# TOUG.net
KiCad netlist of a schematic drawn in EasyEDA
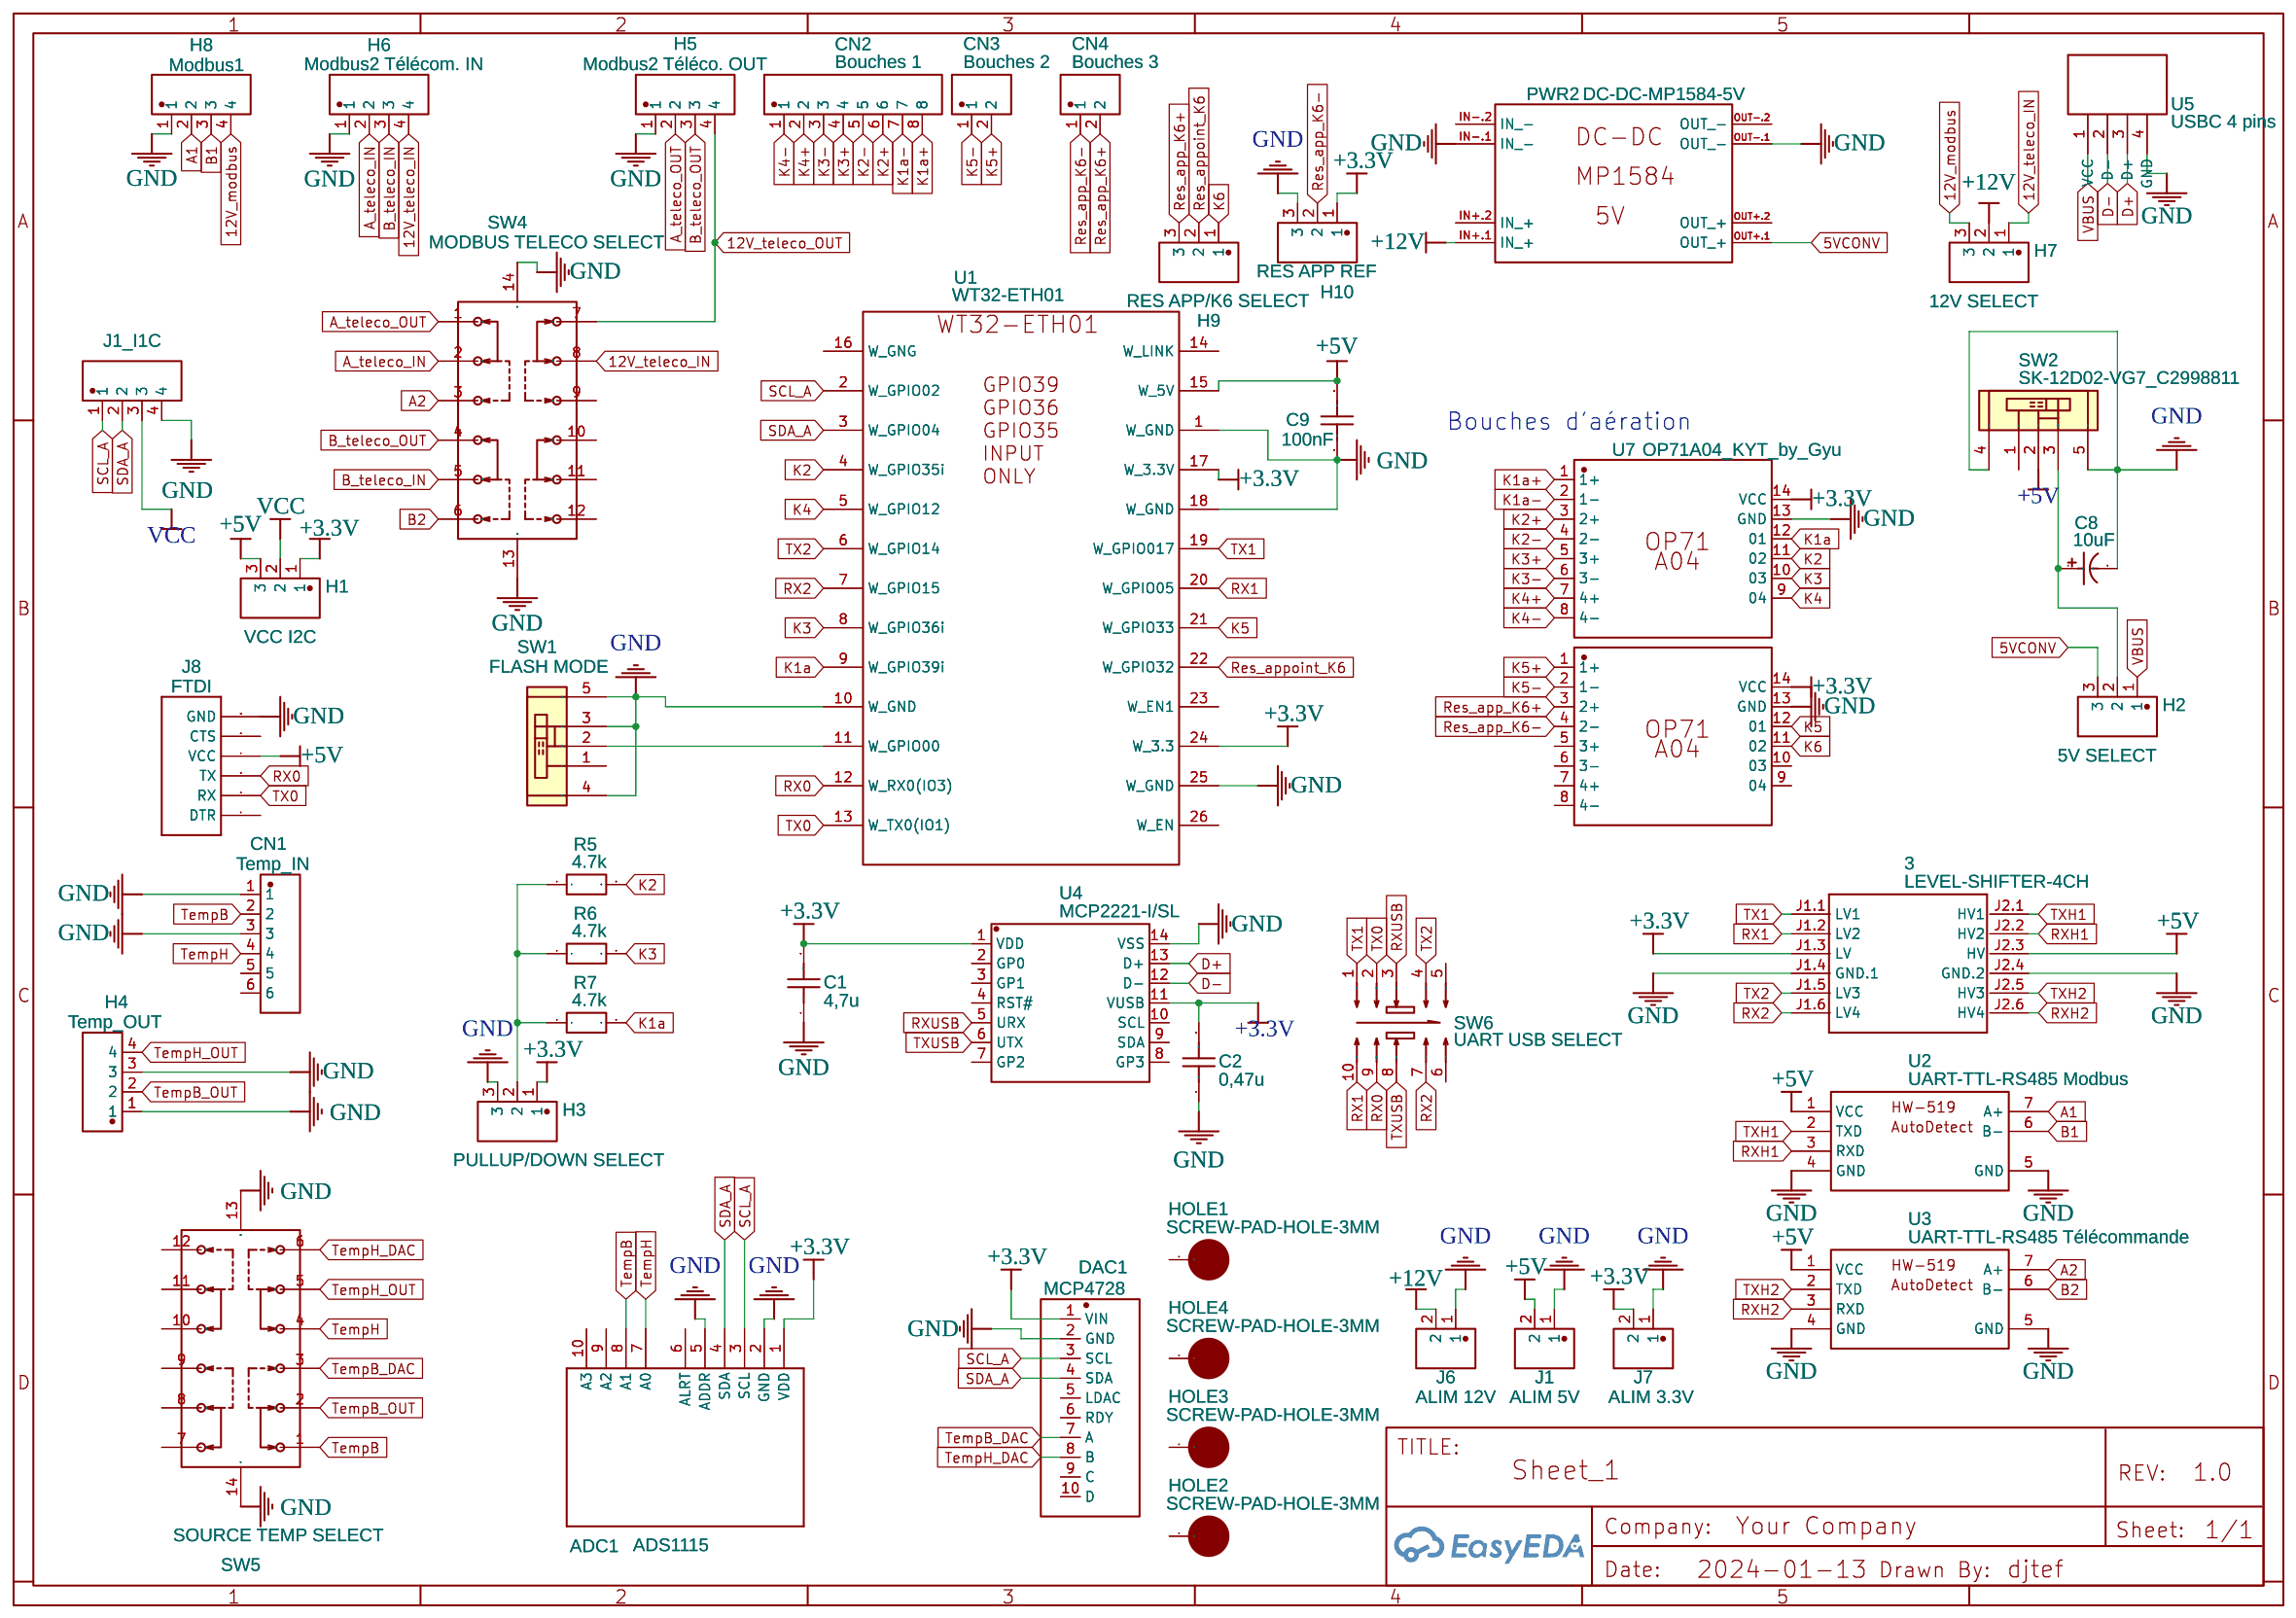
[diagram p0: schematic sheet]

(export (version "E")
  (design (tool "Eeschema 10.0.6"))
  (components
    (comp (ref "3") (value "LEVEL-SHIFTER-4CH") (libsource (lib "") (part "LEVEL-SHIFTER-4CH")))
    (comp (ref "ADC1") (value "ADS1115") (libsource (lib "") (part "ADC-4CH-ADS1115")))
    (comp (ref "C1") (value "4,7u") (libsource (lib "") (part "C_RAD-0.1_US")))
    (comp (ref "C2") (value "0,47u") (libsource (lib "") (part "C_RAD-0.1_US")))
    (comp (ref "C8")
      (value "10uF")
      (fields
        (field (name "Manufacturer Part") "GR106M050D11RR0VK2FP0")
        (field (name "Manufacturer") "CX(承兴)")
      )
      (libsource (lib "") (part "electrolytic capacitor 10UF 50V high frequency"))
    )
    (comp (ref "C9")
      (value "100nF")
      (fields (field (name "Manufacturer Part") "PE104J2A0501") (field (name "Manufacturer") "KYET(科雅)"))
      (libsource (lib "") (part "PE104J2A0501"))
    )
    (comp (ref "CN1")
      (value "Temp_IN")
      (fields (field (name "Manufacturer Part") "S06B-XASK-1(LF)(SN)") (field (name "Manufacturer") "JST"))
      (libsource (lib "") (part "S06B-XASK-1(LF)(SN)"))
    )
    (comp (ref "CN2")
      (value "Bouches 1")
      (fields (field (name "Manufacturer Part") "KF2EDGR-2.54-8P") (field (name "Manufacturer") "KEFA(科发)"))
      (libsource (lib "") (part "KF2EDGR-2.54-8P"))
    )
    (comp (ref "CN3")
      (value "Bouches 2")
      (fields (field (name "Manufacturer Part") "KF2EDGR-2.54-2P") (field (name "Manufacturer") "KEFA(科发)"))
      (libsource (lib "") (part "KF2EDGR-2.54-2P"))
    )
    (comp (ref "CN4")
      (value "Bouches 3")
      (fields (field (name "Manufacturer Part") "KF2EDGR-2.54-2P") (field (name "Manufacturer") "KEFA(科发)"))
      (libsource (lib "") (part "KF2EDGR-2.54-2P"))
    )
    (comp (ref "DAC1")
      (value "MCP4728")
      (fields (field (name "Manufacturer Part") "GY-MCP4728") (field (name "Manufacturer") "Aliexpress"))
      (libsource (lib "") (part "GY-MCP4728"))
    )
    (comp (ref "H1")
      (value "VCC I2C")
      (fields
        (field (name "Manufacturer Part") "DZ254R-11-03-63")
        (field (name "Manufacturer") "DEALON(德艺隆)")
      )
      (libsource (lib "") (part "DZ254R-11-03-63"))
    )
    (comp (ref "H2")
      (value "5V SELECT")
      (fields
        (field (name "Manufacturer Part") "DZ254R-11-03-63")
        (field (name "Manufacturer") "DEALON(德艺隆)")
      )
      (libsource (lib "") (part "DZ254R-11-03-63"))
    )
    (comp (ref "H3")
      (value "PULLUP/DOWN SELECT")
      (fields
        (field (name "Manufacturer Part") "DZ254R-11-03-63")
        (field (name "Manufacturer") "DEALON(德艺隆)")
      )
      (libsource (lib "") (part "DZ254R-11-03-63"))
    )
    (comp (ref "H4")
      (value "Temp_OUT")
      (fields (field (name "Manufacturer Part") "2.54-4P WZDK") (field (name "Manufacturer") "SHOU HAN(首韩)"))
      (libsource (lib "") (part "XH-2.54-4P_2"))
    )
    (comp (ref "H5")
      (value "Modbus2 Téléco. OUT")
      (fields (field (name "Manufacturer Part") "DL25018-4AWD-S") (field (name "Manufacturer") "DLL"))
      (libsource (lib "") (part "XH-2.54-4P"))
    )
    (comp (ref "H6")
      (value "Modbus2 Télécom. IN")
      (fields (field (name "Manufacturer Part") "2.54-4P WZDK") (field (name "Manufacturer") "SHOU HAN(首韩)"))
      (libsource (lib "") (part "XH-2.54-4P"))
    )
    (comp (ref "H7")
      (value "12V SELECT")
      (fields
        (field (name "Manufacturer Part") "DZ254R-11-03-63")
        (field (name "Manufacturer") "DEALON(德艺隆)")
      )
      (libsource (lib "") (part "DZ254R-11-03-63"))
    )
    (comp (ref "H8")
      (value "Modbus1")
      (fields (field (name "Manufacturer Part") "2.54-4P WZDK") (field (name "Manufacturer") "SHOU HAN(首韩)"))
      (libsource (lib "") (part "XH-2.54-4P"))
    )
    (comp (ref "H9")
      (value "RES APP/K6 SELECT")
      (fields
        (field (name "Manufacturer Part") "DZ254R-11-03-63")
        (field (name "Manufacturer") "DEALON(德艺隆)")
      )
      (libsource (lib "") (part "DZ254R-11-03-63"))
    )
    (comp (ref "H10")
      (value "RES APP REF")
      (fields
        (field (name "Manufacturer Part") "DZ254R-11-03-63")
        (field (name "Manufacturer") "DEALON(德艺隆)")
      )
      (libsource (lib "") (part "DZ254R-11-03-63"))
    )
    (comp (ref "HOLE1") (value "SCREW-PAD-HOLE-3MM") (libsource (lib "") (part "SCREW-PAD-HOLE-3MM")))
    (comp (ref "HOLE2") (value "SCREW-PAD-HOLE-3MM") (libsource (lib "") (part "SCREW-PAD-HOLE-3MM")))
    (comp (ref "HOLE3") (value "SCREW-PAD-HOLE-3MM") (libsource (lib "") (part "SCREW-PAD-HOLE-3MM")))
    (comp (ref "HOLE4") (value "SCREW-PAD-HOLE-3MM") (libsource (lib "") (part "SCREW-PAD-HOLE-3MM")))
    (comp (ref "J1")
      (value "ALIM 5V")
      (fields (field (name "Manufacturer Part") "KF2EDGR-5.08-2P") (field (name "Manufacturer") "KEFA(科发)"))
      (libsource (lib "") (part "KF2EDGR-5.08-2P"))
    )
    (comp (ref "J1_I1C")
      (value "I2C")
      (fields (field (name "Manufacturer Part") "2.54-4P WZDK") (field (name "Manufacturer") "SHOU HAN(首韩)"))
      (libsource (lib "") (part "XH-2.54-4P_1"))
    )
    (comp (ref "J6")
      (value "ALIM 12V")
      (fields (field (name "Manufacturer Part") "KF301-5.0-2P") (field (name "Manufacturer") "KEFA(科发)"))
      (libsource (lib "") (part "KF301-5.0-2P"))
    )
    (comp (ref "J7")
      (value "ALIM 3.3V")
      (fields (field (name "Manufacturer Part") "KF2EDGR-5.08-2P") (field (name "Manufacturer") "KEFA(科发)"))
      (libsource (lib "") (part "KF2EDGR-5.08-2P"))
    )
    (comp (ref "J8") (value "FTDI") (libsource (lib "") (part "FTDI HEADERX6")))
    (comp (ref "PWR2") (value "DC-DC-MP1584-5V") (libsource (lib "") (part "DC-DC-MP1584-5V")))
    (comp (ref "R5")
      (value "4.7k")
      (fields (field (name "Manufacturer Part") "CR1/4W-4K7±5%-ST52") (field (name "Manufacturer") "VO(翔胜)"))
      (libsource (lib "") (part "R_AXIAL-1.0_EU"))
    )
    (comp (ref "R6")
      (value "4.7k")
      (fields (field (name "Manufacturer Part") "CR1/4W-4K7±5%-ST52") (field (name "Manufacturer") "VO(翔胜)"))
      (libsource (lib "") (part "R_AXIAL-1.0_EU"))
    )
    (comp (ref "R7")
      (value "4.7k")
      (fields (field (name "Manufacturer Part") "CR1/4W-4K7±5%-ST52") (field (name "Manufacturer") "VO(翔胜)"))
      (libsource (lib "") (part "R_AXIAL-1.0_EU"))
    )
    (comp (ref "SW1")
      (value "FLASH MODE")
      (fields (field (name "Manufacturer Part") "SK-12D02-VG7") (field (name "Manufacturer") "DEALON(德艺隆)"))
      (libsource (lib "") (part "SK-12D02-VG7_C2998811"))
    )
    (comp (ref "SW2")
      (value "SK-12D02-VG7_C2998811")
      (fields (field (name "Manufacturer Part") "SK-12D02-VG7") (field (name "Manufacturer") "DEALON(德艺隆)"))
      (libsource (lib "") (part "SK-12D02-VG7_C2998811_1"))
    )
    (comp (ref "SW4")
      (value "MODBUS TELECO SELECT")
      (fields
        (field (name "Manufacturer Part") "KH-SS42D02-G3")
        (field (name "Manufacturer") "kinghelm(金航标)")
      )
      (libsource (lib "") (part "KH-SS42D02-G3"))
    )
    (comp (ref "SW5")
      (value "SOURCE TEMP SELECT")
      (fields
        (field (name "Manufacturer Part") "KH-SS42D02-G3")
        (field (name "Manufacturer") "kinghelm(金航标)")
      )
      (libsource (lib "") (part "KH-SS42D02-G3_1"))
    )
    (comp (ref "SW6")
      (value "UART USB SELECT")
      (fields (field (name "Manufacturer Part") "SS-24H03-G070") (field (name "Manufacturer") "G-Switch(品赞)"))
      (libsource (lib "") (part "SS-24H03-G070"))
    )
    (comp (ref "U1")
      (value "WT32-ETH01")
      (fields (field (name "Manufacturer") "Wireless-Tag"))
      (libsource (lib "") (part "WT32-ETH01"))
    )
    (comp (ref "U2") (value "UART-TTL-RS485 Modbus") (libsource (lib "") (part "UART-TTL-RS485_HW-519")))
    (comp (ref "U3")
      (value "UART-TTL-RS485 Télécommande")
      (libsource (lib "") (part "UART-TTL-RS485_HW-519"))
    )
    (comp (ref "U4")
      (value "MCP2221-I/SL")
      (fields (field (name "Manufacturer") "MICROCHIP(美国微芯)"))
      (libsource (lib "") (part "MCP2221-I/SL"))
    )
    (comp (ref "U5") (value "USBC 4 pins") (libsource (lib "") (part "USBC 4 pins")))
    (comp (ref "U7") (value "OP71A04_KYT_by_Gyu") (libsource (lib "") (part "OP71A04_KYT_by_Gyu")))
    (comp (ref "U14") (value "OP71A04_KYT_by_Gyu") (libsource (lib "") (part "OP71A04_KYT_by_Gyu")))
  )
  (nets
    (net (code "1") (name "+3.3V") (class "Default")
      (node (ref "3") (pin "J1.3") (pinfunction "LV_J1.3") (pintype "bidirectional"))
      (node (ref "ADC1") (pin "1") (pinfunction "VDD_1") (pintype "bidirectional"))
      (node (ref "C1") (pin "2") (pinfunction "2_2") (pintype "unspecified"))
      (node (ref "C2") (pin "2") (pinfunction "2_2") (pintype "unspecified"))
      (node (ref "DAC1") (pin "1") (pinfunction "VIN_1") (pintype "unspecified"))
      (node (ref "H1") (pin "1") (pinfunction "1_1") (pintype "unspecified"))
      (node (ref "H10") (pin "1") (pinfunction "1_1") (pintype "unspecified"))
      (node (ref "H3") (pin "1") (pinfunction "1_1") (pintype "unspecified"))
      (node (ref "J7") (pin "2") (pinfunction "2_2") (pintype "unspecified"))
      (node (ref "U1") (pin "17") (pinfunction "W_3.3V_17") (pintype "unspecified"))
      (node (ref "U1") (pin "24") (pinfunction "W_3.3_24") (pintype "unspecified"))
      (node (ref "U14") (pin "14") (pinfunction "VCC_14") (pintype "unspecified"))
      (node (ref "U4") (pin "1") (pinfunction "VDD_1") (pintype "unspecified"))
      (node (ref "U4") (pin "11") (pinfunction "VUSB_11") (pintype "unspecified"))
      (node (ref "U7") (pin "14") (pinfunction "VCC_14") (pintype "unspecified"))
    )
    (net (code "2") (name "+5V") (class "Default")
      (node (ref "3") (pin "J2.3") (pinfunction "HV_J2.3") (pintype "bidirectional"))
      (node (ref "C9") (pin "2") (pinfunction "2_2") (pintype "unspecified"))
      (node (ref "H1") (pin "3") (pinfunction "3_3") (pintype "unspecified"))
      (node (ref "J1") (pin "2") (pinfunction "2_2") (pintype "unspecified"))
      (node (ref "J8") (pin "4") (pinfunction "VCC_4") (pintype "unspecified"))
      (node (ref "SW2") (pin "2") (pinfunction "2_2") (pintype "input"))
      (node (ref "U1") (pin "15") (pinfunction "W_5V_15") (pintype "unspecified"))
      (node (ref "U2") (pin "1") (pinfunction "VCC_1") (pintype "unspecified"))
      (node (ref "U3") (pin "1") (pinfunction "VCC_1") (pintype "unspecified"))
    )
    (net (code "3") (name "+12V") (class "Default")
      (node (ref "H7") (pin "2") (pinfunction "2_2") (pintype "unspecified"))
      (node (ref "J6") (pin "2") (pinfunction "2_2") (pintype "unspecified"))
      (node (ref "PWR2") (pin "IN+.1") (pinfunction "IN_+_IN+.1") (pintype "unspecified"))
    )
    (net (code "4") (name "5VCONV") (class "Default")
      (node (ref "H2") (pin "3") (pinfunction "3_3") (pintype "unspecified"))
      (node (ref "PWR2") (pin "OUT+.1") (pinfunction "OUT_+_OUT+.1") (pintype "unspecified"))
    )
    (net (code "5") (name "12V_modbus") (class "Default")
      (node (ref "H7") (pin "3") (pinfunction "3_3") (pintype "unspecified"))
      (node (ref "H8") (pin "4") (pinfunction "4_4") (pintype "unspecified"))
    )
    (net (code "6") (name "12V_teleco_IN") (class "Default")
      (node (ref "H6") (pin "4") (pinfunction "4_4") (pintype "unspecified"))
      (node (ref "H7") (pin "1") (pinfunction "1_1") (pintype "unspecified"))
      (node (ref "SW4") (pin "8") (pinfunction "8_8") (pintype "unspecified"))
    )
    (net (code "7") (name "12V_teleco_OUT") (class "Default")
      (node (ref "H5") (pin "4") (pinfunction "4_4") (pintype "unspecified"))
      (node (ref "SW4") (pin "7") (pinfunction "7_7") (pintype "unspecified"))
    )
    (net (code "8") (name "A1") (class "Default")
      (node (ref "H8") (pin "2") (pinfunction "2_2") (pintype "unspecified"))
      (node (ref "U2") (pin "7") (pinfunction "A+_7") (pintype "unspecified"))
    )
    (net (code "9") (name "A2") (class "Default")
      (node (ref "SW4") (pin "3") (pinfunction "3_3") (pintype "unspecified"))
      (node (ref "U3") (pin "7") (pinfunction "A+_7") (pintype "unspecified"))
    )
    (net (code "10") (name "A_teleco_IN") (class "Default")
      (node (ref "H6") (pin "2") (pinfunction "2_2") (pintype "unspecified"))
      (node (ref "SW4") (pin "2") (pinfunction "2_2") (pintype "unspecified"))
    )
    (net (code "11") (name "A_teleco_OUT") (class "Default")
      (node (ref "H5") (pin "2") (pinfunction "2_2") (pintype "unspecified"))
      (node (ref "SW4") (pin "1") (pinfunction "1_1") (pintype "unspecified"))
    )
    (net (code "12") (name "B1") (class "Default")
      (node (ref "H8") (pin "3") (pinfunction "3_3") (pintype "unspecified"))
      (node (ref "U2") (pin "6") (pinfunction "B-_6") (pintype "unspecified"))
    )
    (net (code "13") (name "B2") (class "Default")
      (node (ref "SW4") (pin "6") (pinfunction "6_6") (pintype "unspecified"))
      (node (ref "U3") (pin "6") (pinfunction "B-_6") (pintype "unspecified"))
    )
    (net (code "14") (name "B_teleco_IN") (class "Default")
      (node (ref "H6") (pin "3") (pinfunction "3_3") (pintype "unspecified"))
      (node (ref "SW4") (pin "5") (pinfunction "5_5") (pintype "unspecified"))
    )
    (net (code "15") (name "B_teleco_OUT") (class "Default")
      (node (ref "H5") (pin "3") (pinfunction "3_3") (pintype "unspecified"))
      (node (ref "SW4") (pin "4") (pinfunction "4_4") (pintype "unspecified"))
    )
    (net (code "16") (name "D+") (class "Default")
      (node (ref "U4") (pin "13") (pinfunction "D+_13") (pintype "unspecified"))
      (node (ref "U5") (pin "3") (pinfunction "D+_3") (pintype "unspecified"))
    )
    (net (code "17") (name "D-") (class "Default")
      (node (ref "U4") (pin "12") (pinfunction "D-_12") (pintype "unspecified"))
      (node (ref "U5") (pin "2") (pinfunction "D-_2") (pintype "unspecified"))
    )
    (net (code "18") (name "GND") (class "Default")
      (node (ref "3") (pin "J1.4") (pinfunction "GND.1_J1.4") (pintype "bidirectional"))
      (node (ref "3") (pin "J2.4") (pinfunction "GND.2_J2.4") (pintype "bidirectional"))
      (node (ref "ADC1") (pin "2") (pinfunction "GND_2") (pintype "bidirectional"))
      (node (ref "ADC1") (pin "5") (pinfunction "ADDR_5") (pintype "bidirectional"))
      (node (ref "C1") (pin "1") (pinfunction "1_1") (pintype "unspecified"))
      (node (ref "C2") (pin "1") (pinfunction "1_1") (pintype "unspecified"))
      (node (ref "C8") (pin "2") (pinfunction "2_2") (pintype "input"))
      (node (ref "C9") (pin "1") (pinfunction "1_1") (pintype "unspecified"))
      (node (ref "CN1") (pin "1") (pinfunction "1_1") (pintype "unspecified"))
      (node (ref "CN1") (pin "3") (pinfunction "3_3") (pintype "unspecified"))
      (node (ref "DAC1") (pin "2") (pinfunction "GND_2") (pintype "unspecified"))
      (node (ref "H10") (pin "3") (pinfunction "3_3") (pintype "unspecified"))
      (node (ref "H3") (pin "3") (pinfunction "3_3") (pintype "unspecified"))
      (node (ref "H4") (pin "1") (pinfunction "1_1") (pintype "unspecified"))
      (node (ref "H4") (pin "3") (pinfunction "3_3") (pintype "unspecified"))
      (node (ref "H5") (pin "1") (pinfunction "1_1") (pintype "unspecified"))
      (node (ref "H6") (pin "1") (pinfunction "1_1") (pintype "unspecified"))
      (node (ref "H8") (pin "1") (pinfunction "1_1") (pintype "unspecified"))
      (node (ref "J1") (pin "1") (pinfunction "1_1") (pintype "unspecified"))
      (node (ref "J1_I1C") (pin "4") (pinfunction "4_4") (pintype "unspecified"))
      (node (ref "J6") (pin "1") (pinfunction "1_1") (pintype "unspecified"))
      (node (ref "J7") (pin "1") (pinfunction "1_1") (pintype "unspecified"))
      (node (ref "J8") (pin "6") (pinfunction "GND_6") (pintype "unspecified"))
      (node (ref "PWR2") (pin "IN-.1") (pinfunction "IN_-_IN-.1") (pintype "unspecified"))
      (node (ref "PWR2") (pin "OUT-.1") (pinfunction "OUT_-_OUT-.1") (pintype "unspecified"))
      (node (ref "SW1") (pin "3") (pinfunction "3_3") (pintype "input"))
      (node (ref "SW1") (pin "4") (pinfunction "4_4") (pintype "input"))
      (node (ref "SW1") (pin "5") (pinfunction "5_5") (pintype "input"))
      (node (ref "SW2") (pin "4") (pinfunction "4_4") (pintype "input"))
      (node (ref "SW2") (pin "5") (pinfunction "5_5") (pintype "input"))
      (node (ref "SW4") (pin "13") (pinfunction "13_13") (pintype "unspecified"))
      (node (ref "SW4") (pin "14") (pinfunction "14_14") (pintype "unspecified"))
      (node (ref "SW5") (pin "13") (pinfunction "13_13") (pintype "unspecified"))
      (node (ref "SW5") (pin "14") (pinfunction "14_14") (pintype "unspecified"))
      (node (ref "U1") (pin "1") (pinfunction "W_GND_1") (pintype "unspecified"))
      (node (ref "U1") (pin "10") (pinfunction "W_GND_10") (pintype "unspecified"))
      (node (ref "U1") (pin "18") (pinfunction "W_GND_18") (pintype "unspecified"))
      (node (ref "U1") (pin "25") (pinfunction "W_GND_25") (pintype "unspecified"))
      (node (ref "U14") (pin "13") (pinfunction "GND_13") (pintype "unspecified"))
      (node (ref "U2") (pin "4") (pinfunction "GND_4") (pintype "unspecified"))
      (node (ref "U2") (pin "5") (pinfunction "GND_5") (pintype "unspecified"))
      (node (ref "U3") (pin "4") (pinfunction "GND_4") (pintype "unspecified"))
      (node (ref "U3") (pin "5") (pinfunction "GND_5") (pintype "unspecified"))
      (node (ref "U4") (pin "14") (pinfunction "VSS_14") (pintype "unspecified"))
      (node (ref "U5") (pin "4") (pinfunction "GND_4") (pintype "unspecified"))
      (node (ref "U7") (pin "13") (pinfunction "GND_13") (pintype "unspecified"))
    )
    (net (code "19") (name "K1a") (class "Default")
      (node (ref "R7") (pin "2") (pinfunction "2_2") (pintype "unspecified"))
      (node (ref "U1") (pin "9") (pinfunction "W_GPIO39i_9") (pintype "unspecified"))
      (node (ref "U7") (pin "12") (pinfunction "01_12") (pintype "unspecified"))
    )
    (net (code "20") (name "K1a+") (class "Default")
      (node (ref "CN2") (pin "8") (pinfunction "8_8") (pintype "unspecified"))
      (node (ref "U7") (pin "1") (pinfunction "1+_1") (pintype "unspecified"))
    )
    (net (code "21") (name "K1a-") (class "Default")
      (node (ref "CN2") (pin "7") (pinfunction "7_7") (pintype "unspecified"))
      (node (ref "U7") (pin "2") (pinfunction "1-_2") (pintype "unspecified"))
    )
    (net (code "22") (name "K2") (class "Default")
      (node (ref "R5") (pin "2") (pinfunction "2_2") (pintype "unspecified"))
      (node (ref "U1") (pin "4") (pinfunction "W_GPIO35i_4") (pintype "unspecified"))
      (node (ref "U7") (pin "11") (pinfunction "02_11") (pintype "unspecified"))
    )
    (net (code "23") (name "K2+") (class "Default")
      (node (ref "CN2") (pin "6") (pinfunction "6_6") (pintype "unspecified"))
      (node (ref "U7") (pin "3") (pinfunction "2+_3") (pintype "unspecified"))
    )
    (net (code "24") (name "K2-") (class "Default")
      (node (ref "CN2") (pin "5") (pinfunction "5_5") (pintype "unspecified"))
      (node (ref "U7") (pin "4") (pinfunction "2-_4") (pintype "unspecified"))
    )
    (net (code "25") (name "K3") (class "Default")
      (node (ref "R6") (pin "2") (pinfunction "2_2") (pintype "unspecified"))
      (node (ref "U1") (pin "8") (pinfunction "W_GPIO36i_8") (pintype "unspecified"))
      (node (ref "U7") (pin "10") (pinfunction "03_10") (pintype "unspecified"))
    )
    (net (code "26") (name "K3+") (class "Default")
      (node (ref "CN2") (pin "4") (pinfunction "4_4") (pintype "unspecified"))
      (node (ref "U7") (pin "5") (pinfunction "3+_5") (pintype "unspecified"))
    )
    (net (code "27") (name "K3-") (class "Default")
      (node (ref "CN2") (pin "3") (pinfunction "3_3") (pintype "unspecified"))
      (node (ref "U7") (pin "6") (pinfunction "3-_6") (pintype "unspecified"))
    )
    (net (code "28") (name "K4") (class "Default")
      (node (ref "U1") (pin "5") (pinfunction "W_GPIO12_5") (pintype "unspecified"))
      (node (ref "U7") (pin "9") (pinfunction "04_9") (pintype "unspecified"))
    )
    (net (code "29") (name "K4+") (class "Default")
      (node (ref "CN2") (pin "2") (pinfunction "2_2") (pintype "unspecified"))
      (node (ref "U7") (pin "7") (pinfunction "4+_7") (pintype "unspecified"))
    )
    (net (code "30") (name "K4-") (class "Default")
      (node (ref "CN2") (pin "1") (pinfunction "1_1") (pintype "unspecified"))
      (node (ref "U7") (pin "8") (pinfunction "4-_8") (pintype "unspecified"))
    )
    (net (code "31") (name "K5") (class "Default")
      (node (ref "U1") (pin "21") (pinfunction "W_GPIO33_21") (pintype "unspecified"))
      (node (ref "U14") (pin "12") (pinfunction "01_12") (pintype "unspecified"))
    )
    (net (code "32") (name "K5+") (class "Default")
      (node (ref "CN3") (pin "2") (pinfunction "2_2") (pintype "unspecified"))
      (node (ref "U14") (pin "1") (pinfunction "1+_1") (pintype "unspecified"))
    )
    (net (code "33") (name "K5-") (class "Default")
      (node (ref "CN3") (pin "1") (pinfunction "1_1") (pintype "unspecified"))
      (node (ref "U14") (pin "2") (pinfunction "1-_2") (pintype "unspecified"))
    )
    (net (code "34") (name "K6") (class "Default")
      (node (ref "H9") (pin "1") (pinfunction "1_1") (pintype "unspecified"))
      (node (ref "U14") (pin "11") (pinfunction "02_11") (pintype "unspecified"))
    )
    (net (code "35") (name "Net-(C8-Pad1)") (class "Default")
      (node (ref "C8") (pin "1") (pinfunction "1_1") (pintype "input"))
      (node (ref "H2") (pin "2") (pinfunction "2_2") (pintype "unspecified"))
      (node (ref "SW2") (pin "3") (pinfunction "3_3") (pintype "input"))
    )
    (net (code "36") (name "Net-(H3-Pad2)") (class "Default")
      (node (ref "H3") (pin "2") (pinfunction "2_2") (pintype "unspecified"))
      (node (ref "R5") (pin "1") (pinfunction "1_1") (pintype "unspecified"))
      (node (ref "R6") (pin "1") (pinfunction "1_1") (pintype "unspecified"))
      (node (ref "R7") (pin "1") (pinfunction "1_1") (pintype "unspecified"))
    )
    (net (code "37") (name "Net-(U1-W_GPIO00)") (class "Default")
      (node (ref "SW1") (pin "2") (pinfunction "2_2") (pintype "input"))
      (node (ref "U1") (pin "11") (pinfunction "W_GPIO00_11") (pintype "unspecified"))
    )
    (net (code "38") (name "RX0") (class "Default")
      (node (ref "J8") (pin "3") (pinfunction "TX_3") (pintype "unspecified"))
      (node (ref "SW6") (pin "9") (pinfunction "9_9") (pintype "unspecified"))
      (node (ref "U1") (pin "12") (pinfunction "W_RX0(IO3)_12") (pintype "unspecified"))
    )
    (net (code "39") (name "RX1") (class "Default")
      (node (ref "3") (pin "J1.2") (pinfunction "LV2_J1.2") (pintype "bidirectional"))
      (node (ref "SW6") (pin "10") (pinfunction "10_10") (pintype "unspecified"))
      (node (ref "U1") (pin "20") (pinfunction "W_GPIO05_20") (pintype "unspecified"))
    )
    (net (code "40") (name "RX2") (class "Default")
      (node (ref "3") (pin "J1.6") (pinfunction "LV4_J1.6") (pintype "bidirectional"))
      (node (ref "SW6") (pin "7") (pinfunction "7_7") (pintype "unspecified"))
      (node (ref "U1") (pin "7") (pinfunction "W_GPIO15_7") (pintype "unspecified"))
    )
    (net (code "41") (name "RXH1") (class "Default")
      (node (ref "3") (pin "J2.2") (pinfunction "HV2_J2.2") (pintype "bidirectional"))
      (node (ref "U2") (pin "3") (pinfunction "RXD_3") (pintype "unspecified"))
    )
    (net (code "42") (name "RXH2") (class "Default")
      (node (ref "3") (pin "J2.6") (pinfunction "HV4_J2.6") (pintype "bidirectional"))
      (node (ref "U3") (pin "3") (pinfunction "RXD_3") (pintype "unspecified"))
    )
    (net (code "43") (name "RXUSB") (class "Default")
      (node (ref "SW6") (pin "3") (pinfunction "3_3") (pintype "unspecified"))
      (node (ref "U4") (pin "5") (pinfunction "URX_5") (pintype "unspecified"))
    )
    (net (code "44") (name "Res_app_K6+") (class "Default")
      (node (ref "CN4") (pin "2") (pinfunction "2_2") (pintype "unspecified"))
      (node (ref "H9") (pin "3") (pinfunction "3_3") (pintype "unspecified"))
      (node (ref "U14") (pin "3") (pinfunction "2+_3") (pintype "unspecified"))
    )
    (net (code "45") (name "Res_app_K6-") (class "Default")
      (node (ref "CN4") (pin "1") (pinfunction "1_1") (pintype "unspecified"))
      (node (ref "H10") (pin "2") (pinfunction "2_2") (pintype "unspecified"))
      (node (ref "U14") (pin "4") (pinfunction "2-_4") (pintype "unspecified"))
    )
    (net (code "46") (name "Res_appoint_K6") (class "Default")
      (node (ref "H9") (pin "2") (pinfunction "2_2") (pintype "unspecified"))
      (node (ref "U1") (pin "22") (pinfunction "W_GPIO32_22") (pintype "unspecified"))
    )
    (net (code "47") (name "SCL_A") (class "Default")
      (node (ref "ADC1") (pin "3") (pinfunction "SCL_3") (pintype "bidirectional"))
      (node (ref "DAC1") (pin "3") (pinfunction "SCL_3") (pintype "unspecified"))
      (node (ref "J1_I1C") (pin "1") (pinfunction "1_1") (pintype "unspecified"))
      (node (ref "U1") (pin "2") (pinfunction "W_GPIO02_2") (pintype "unspecified"))
    )
    (net (code "48") (name "SDA_A") (class "Default")
      (node (ref "ADC1") (pin "4") (pinfunction "SDA_4") (pintype "bidirectional"))
      (node (ref "DAC1") (pin "4") (pinfunction "SDA_4") (pintype "unspecified"))
      (node (ref "J1_I1C") (pin "2") (pinfunction "2_2") (pintype "unspecified"))
      (node (ref "U1") (pin "3") (pinfunction "W_GPIO04_3") (pintype "unspecified"))
    )
    (net (code "49") (name "TX0") (class "Default")
      (node (ref "J8") (pin "2") (pinfunction "RX_2") (pintype "unspecified"))
      (node (ref "SW6") (pin "2") (pinfunction "2_2") (pintype "unspecified"))
      (node (ref "U1") (pin "13") (pinfunction "W_TX0(IO1)_13") (pintype "unspecified"))
    )
    (net (code "50") (name "TX1") (class "Default")
      (node (ref "3") (pin "J1.1") (pinfunction "LV1_J1.1") (pintype "bidirectional"))
      (node (ref "SW6") (pin "1") (pinfunction "1_1") (pintype "unspecified"))
      (node (ref "U1") (pin "19") (pinfunction "W_GPIO017_19") (pintype "unspecified"))
    )
    (net (code "51") (name "TX2") (class "Default")
      (node (ref "3") (pin "J1.5") (pinfunction "LV3_J1.5") (pintype "bidirectional"))
      (node (ref "SW6") (pin "4") (pinfunction "4_4") (pintype "unspecified"))
      (node (ref "U1") (pin "6") (pinfunction "W_GPIO14_6") (pintype "unspecified"))
    )
    (net (code "52") (name "TXH1") (class "Default")
      (node (ref "3") (pin "J2.1") (pinfunction "HV1_J2.1") (pintype "bidirectional"))
      (node (ref "U2") (pin "2") (pinfunction "TXD_2") (pintype "unspecified"))
    )
    (net (code "53") (name "TXH2") (class "Default")
      (node (ref "3") (pin "J2.5") (pinfunction "HV3_J2.5") (pintype "bidirectional"))
      (node (ref "U3") (pin "2") (pinfunction "TXD_2") (pintype "unspecified"))
    )
    (net (code "54") (name "TXUSB") (class "Default")
      (node (ref "SW6") (pin "8") (pinfunction "8_8") (pintype "unspecified"))
      (node (ref "U4") (pin "6") (pinfunction "UTX_6") (pintype "unspecified"))
    )
    (net (code "55") (name "TempB") (class "Default")
      (node (ref "ADC1") (pin "8") (pinfunction "A1_8") (pintype "bidirectional"))
      (node (ref "CN1") (pin "2") (pinfunction "2_2") (pintype "unspecified"))
      (node (ref "SW5") (pin "1") (pinfunction "1_1") (pintype "unspecified"))
    )
    (net (code "56") (name "TempB_DAC") (class "Default")
      (node (ref "DAC1") (pin "7") (pinfunction "A_7") (pintype "unspecified"))
      (node (ref "SW5") (pin "3") (pinfunction "3_3") (pintype "unspecified"))
    )
    (net (code "57") (name "TempB_OUT") (class "Default")
      (node (ref "H4") (pin "2") (pinfunction "2_2") (pintype "unspecified"))
      (node (ref "SW5") (pin "2") (pinfunction "2_2") (pintype "unspecified"))
    )
    (net (code "58") (name "TempH") (class "Default")
      (node (ref "ADC1") (pin "7") (pinfunction "A0_7") (pintype "bidirectional"))
      (node (ref "CN1") (pin "4") (pinfunction "4_4") (pintype "unspecified"))
      (node (ref "SW5") (pin "4") (pinfunction "4_4") (pintype "unspecified"))
    )
    (net (code "59") (name "TempH_DAC") (class "Default")
      (node (ref "DAC1") (pin "8") (pinfunction "B_8") (pintype "unspecified"))
      (node (ref "SW5") (pin "6") (pinfunction "6_6") (pintype "unspecified"))
    )
    (net (code "60") (name "TempH_OUT") (class "Default")
      (node (ref "H4") (pin "4") (pinfunction "4_4") (pintype "unspecified"))
      (node (ref "SW5") (pin "5") (pinfunction "5_5") (pintype "unspecified"))
    )
    (net (code "61") (name "VBUS") (class "Default")
      (node (ref "H2") (pin "1") (pinfunction "1_1") (pintype "unspecified"))
      (node (ref "U5") (pin "1") (pinfunction "VCC_1") (pintype "unspecified"))
    )
    (net (code "62") (name "VCC") (class "Default")
      (node (ref "H1") (pin "2") (pinfunction "2_2") (pintype "unspecified"))
      (node (ref "J1_I1C") (pin "3") (pinfunction "3_3") (pintype "unspecified"))
    )
    (net (code "63") (name "unconnected-(ADC1-A2-Pad9)") (class "Default")
      (node (ref "ADC1") (pin "9") (pinfunction "A2_9") (pintype "bidirectional"))
    )
    (net (code "64") (name "unconnected-(ADC1-A3-Pad10)") (class "Default")
      (node (ref "ADC1") (pin "10") (pinfunction "A3_10") (pintype "bidirectional"))
    )
    (net (code "65") (name "unconnected-(ADC1-ALRT-Pad6)") (class "Default")
      (node (ref "ADC1") (pin "6") (pinfunction "ALRT_6") (pintype "bidirectional"))
    )
    (net (code "66") (name "unconnected-(CN1-Pad5)") (class "Default")
      (node (ref "CN1") (pin "5") (pinfunction "5_5") (pintype "unspecified"))
    )
    (net (code "67") (name "unconnected-(CN1-Pad6)") (class "Default")
      (node (ref "CN1") (pin "6") (pinfunction "6_6") (pintype "unspecified"))
    )
    (net (code "68") (name "unconnected-(DAC1-C-Pad9)") (class "Default")
      (node (ref "DAC1") (pin "9") (pinfunction "C_9") (pintype "unspecified"))
    )
    (net (code "69") (name "unconnected-(DAC1-D-Pad10)") (class "Default")
      (node (ref "DAC1") (pin "10") (pinfunction "D_10") (pintype "unspecified"))
    )
    (net (code "70") (name "unconnected-(DAC1-LDAC-Pad5)") (class "Default")
      (node (ref "DAC1") (pin "5") (pinfunction "LDAC_5") (pintype "unspecified"))
    )
    (net (code "71") (name "unconnected-(DAC1-RDY-Pad6)") (class "Default")
      (node (ref "DAC1") (pin "6") (pinfunction "RDY_6") (pintype "unspecified"))
    )
    (net (code "72") (name "unconnected-(HOLE1-Pad1)") (class "Default")
      (node (ref "HOLE1") (pin "1") (pinfunction "1_1") (pintype "unspecified"))
    )
    (net (code "73") (name "unconnected-(HOLE2-Pad1)") (class "Default")
      (node (ref "HOLE2") (pin "1") (pinfunction "1_1") (pintype "unspecified"))
    )
    (net (code "74") (name "unconnected-(HOLE3-Pad1)") (class "Default")
      (node (ref "HOLE3") (pin "1") (pinfunction "1_1") (pintype "unspecified"))
    )
    (net (code "75") (name "unconnected-(HOLE4-Pad1)") (class "Default")
      (node (ref "HOLE4") (pin "1") (pinfunction "1_1") (pintype "unspecified"))
    )
    (net (code "76") (name "unconnected-(J8-CTS-Pad5)") (class "Default")
      (node (ref "J8") (pin "5") (pinfunction "CTS_5") (pintype "unspecified"))
    )
    (net (code "77") (name "unconnected-(J8-DTR-Pad1)") (class "Default")
      (node (ref "J8") (pin "1") (pinfunction "DTR_1") (pintype "unspecified"))
    )
    (net (code "78") (name "unconnected-(PWR2-IN_+-PadIN+.2)") (class "Default")
      (node (ref "PWR2") (pin "IN+.2") (pinfunction "IN_+_IN+.2") (pintype "unspecified"))
    )
    (net (code "79") (name "unconnected-(PWR2-IN_--PadIN-.2)") (class "Default")
      (node (ref "PWR2") (pin "IN-.2") (pinfunction "IN_-_IN-.2") (pintype "unspecified"))
    )
    (net (code "80") (name "unconnected-(PWR2-OUT_+-PadOUT+.2)") (class "Default")
      (node (ref "PWR2") (pin "OUT+.2") (pinfunction "OUT_+_OUT+.2") (pintype "unspecified"))
    )
    (net (code "81") (name "unconnected-(PWR2-OUT_--PadOUT-.2)") (class "Default")
      (node (ref "PWR2") (pin "OUT-.2") (pinfunction "OUT_-_OUT-.2") (pintype "unspecified"))
    )
    (net (code "82") (name "unconnected-(SW1-Pad1)") (class "Default")
      (node (ref "SW1") (pin "1") (pinfunction "1_1") (pintype "input"))
    )
    (net (code "83") (name "unconnected-(SW2-Pad1)") (class "Default")
      (node (ref "SW2") (pin "1") (pinfunction "1_1") (pintype "input"))
    )
    (net (code "84") (name "unconnected-(SW4-Pad9)") (class "Default")
      (node (ref "SW4") (pin "9") (pinfunction "9_9") (pintype "unspecified"))
    )
    (net (code "85") (name "unconnected-(SW4-Pad10)") (class "Default")
      (node (ref "SW4") (pin "10") (pinfunction "10_10") (pintype "unspecified"))
    )
    (net (code "86") (name "unconnected-(SW4-Pad11)") (class "Default")
      (node (ref "SW4") (pin "11") (pinfunction "11_11") (pintype "unspecified"))
    )
    (net (code "87") (name "unconnected-(SW4-Pad12)") (class "Default")
      (node (ref "SW4") (pin "12") (pinfunction "12_12") (pintype "unspecified"))
    )
    (net (code "88") (name "unconnected-(SW5-Pad7)") (class "Default")
      (node (ref "SW5") (pin "7") (pinfunction "7_7") (pintype "unspecified"))
    )
    (net (code "89") (name "unconnected-(SW5-Pad8)") (class "Default")
      (node (ref "SW5") (pin "8") (pinfunction "8_8") (pintype "unspecified"))
    )
    (net (code "90") (name "unconnected-(SW5-Pad9)") (class "Default")
      (node (ref "SW5") (pin "9") (pinfunction "9_9") (pintype "unspecified"))
    )
    (net (code "91") (name "unconnected-(SW5-Pad10)") (class "Default")
      (node (ref "SW5") (pin "10") (pinfunction "10_10") (pintype "unspecified"))
    )
    (net (code "92") (name "unconnected-(SW5-Pad11)") (class "Default")
      (node (ref "SW5") (pin "11") (pinfunction "11_11") (pintype "unspecified"))
    )
    (net (code "93") (name "unconnected-(SW5-Pad12)") (class "Default")
      (node (ref "SW5") (pin "12") (pinfunction "12_12") (pintype "unspecified"))
    )
    (net (code "94") (name "unconnected-(SW6-Pad5)") (class "Default")
      (node (ref "SW6") (pin "5") (pinfunction "5_5") (pintype "unspecified"))
    )
    (net (code "95") (name "unconnected-(SW6-Pad6)") (class "Default")
      (node (ref "SW6") (pin "6") (pinfunction "6_6") (pintype "unspecified"))
    )
    (net (code "96") (name "unconnected-(U1-W_EN-Pad26)") (class "Default")
      (node (ref "U1") (pin "26") (pinfunction "W_EN_26") (pintype "unspecified"))
    )
    (net (code "97") (name "unconnected-(U1-W_EN1-Pad23)") (class "Default")
      (node (ref "U1") (pin "23") (pinfunction "W_EN1_23") (pintype "unspecified"))
    )
    (net (code "98") (name "unconnected-(U1-W_GNG-Pad16)") (class "Default")
      (node (ref "U1") (pin "16") (pinfunction "W_GNG_16") (pintype "unspecified"))
    )
    (net (code "99") (name "unconnected-(U1-W_LINK-Pad14)") (class "Default")
      (node (ref "U1") (pin "14") (pinfunction "W_LINK_14") (pintype "unspecified"))
    )
    (net (code "100") (name "unconnected-(U4-GP0-Pad2)") (class "Default")
      (node (ref "U4") (pin "2") (pinfunction "GP0_2") (pintype "unspecified"))
    )
    (net (code "101") (name "unconnected-(U4-GP1-Pad3)") (class "Default")
      (node (ref "U4") (pin "3") (pinfunction "GP1_3") (pintype "unspecified"))
    )
    (net (code "102") (name "unconnected-(U4-GP2-Pad7)") (class "Default")
      (node (ref "U4") (pin "7") (pinfunction "GP2_7") (pintype "unspecified"))
    )
    (net (code "103") (name "unconnected-(U4-GP3-Pad8)") (class "Default")
      (node (ref "U4") (pin "8") (pinfunction "GP3_8") (pintype "unspecified"))
    )
    (net (code "104") (name "unconnected-(U4-RST#-Pad4)") (class "Default")
      (node (ref "U4") (pin "4") (pinfunction "RST#_4") (pintype "unspecified"))
    )
    (net (code "105") (name "unconnected-(U4-SCL-Pad10)") (class "Default")
      (node (ref "U4") (pin "10") (pinfunction "SCL_10") (pintype "unspecified"))
    )
    (net (code "106") (name "unconnected-(U4-SDA-Pad9)") (class "Default")
      (node (ref "U4") (pin "9") (pinfunction "SDA_9") (pintype "unspecified"))
    )
    (net (code "107") (name "unconnected-(U14-3+-Pad5)") (class "Default")
      (node (ref "U14") (pin "5") (pinfunction "3+_5") (pintype "unspecified"))
    )
    (net (code "108") (name "unconnected-(U14-3--Pad6)") (class "Default")
      (node (ref "U14") (pin "6") (pinfunction "3-_6") (pintype "unspecified"))
    )
    (net (code "109") (name "unconnected-(U14-03-Pad10)") (class "Default")
      (node (ref "U14") (pin "10") (pinfunction "03_10") (pintype "unspecified"))
    )
    (net (code "110") (name "unconnected-(U14-4+-Pad7)") (class "Default")
      (node (ref "U14") (pin "7") (pinfunction "4+_7") (pintype "unspecified"))
    )
    (net (code "111") (name "unconnected-(U14-4--Pad8)") (class "Default")
      (node (ref "U14") (pin "8") (pinfunction "4-_8") (pintype "unspecified"))
    )
    (net (code "112") (name "unconnected-(U14-04-Pad9)") (class "Default")
      (node (ref "U14") (pin "9") (pinfunction "04_9") (pintype "unspecified"))
    )
  )
)
